# DS3231.net
KiCad netlist of a schematic drawn in Altium Designer
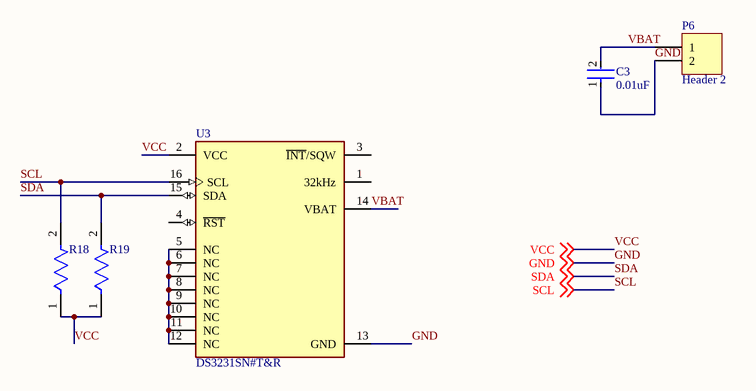
[diagram p0: DS3231.SchDoc]

(export (version "E")
  (design (tool "Eeschema 10.0.6"))
  (components
    (comp (ref "C3")
      (value "0.01uF")
      (footprint "FP-C1206C-EB-MFG")
      (description "1206 C 330nF Ceramic Multilayer Capacitor; 25 VDC; +125degC; X7R Dielec; +/-10%")
      (fields
        (field (name "MANUFACTURER") "KEMET")
        (field (name "MANUFACTURER PART NUMBER") "C1206C334K3RACTU")
      )
      (libsource (lib "Altium Content Vault") (part "b4654b650e69147ec39a6b967a45e02"))
    )
    (comp (ref "P6")
      (value "Header 2")
      (footprint "HDR1X2")
      (description "Header, 2-Pin")
      (fields (field (name "PUBLISHER") "Altium Limited"))
      (libsource (lib "Miscellaneous Connectors") (part "Header 2"))
    )
    (comp (ref "R18")
      (value "~")
      (footprint "FP-CR1206-IPC_B")
      (description "Thick Film Chip Resistors 1206 10kΩ 0.25W 5% 200ppm/°C")
      (fields (field (name "TOLERANCE") "5%"))
      (libsource (lib "Altium Content Vault") (part "1029c3af85768c4190bb7ad29bc67b5"))
    )
    (comp (ref "R19")
      (value "~")
      (footprint "FP-CR1206-IPC_B")
      (description "Thick Film Chip Resistors 1206 10kΩ 0.25W 5% 200ppm/°C")
      (fields (field (name "TOLERANCE") "5%"))
      (libsource (lib "Altium Content Vault") (part "1029c3af85768c4190bb7ad29bc67b5"))
    )
    (comp (ref "U3")
      (value "DS3231SN#T&R")
      (footprint "FP-W16-H2-MFG")
      (description "IC RTC CLK/CALENDAR I2C 16-SOIC")
      (libsource (lib "Altium Content Vault") (part "49e129a02c1e013a88f81c98964c20e"))
    )
  )
  (nets
    (net (code "1") (name "/VBAT") (class "Default")
      (node (ref "C3") (pin "2") (pinfunction "2_2") (pintype "passive"))
      (node (ref "P6") (pin "1") (pinfunction "1_1") (pintype "passive"))
      (node (ref "U3") (pin "14") (pinfunction "VBAT_14") (pintype "power_in"))
    )
    (net (code "2") (name "GND") (class "Default")
      (node (ref "C3") (pin "1") (pinfunction "1_1") (pintype "passive"))
      (node (ref "P6") (pin "2") (pinfunction "2_2") (pintype "passive"))
      (node (ref "U3") (pin "13") (pinfunction "GND_13") (pintype "power_in"))
    )
    (net (code "3") (name "Net-(U3-NC-Pad10)") (class "Default")
      (node (ref "U3") (pin "10") (pinfunction "NC_10") (pintype "passive"))
      (node (ref "U3") (pin "11") (pinfunction "NC_11") (pintype "passive"))
      (node (ref "U3") (pin "12") (pinfunction "NC_12") (pintype "passive"))
      (node (ref "U3") (pin "5") (pinfunction "NC_5") (pintype "passive"))
      (node (ref "U3") (pin "6") (pinfunction "NC_6") (pintype "passive"))
      (node (ref "U3") (pin "7") (pinfunction "NC_7") (pintype "passive"))
      (node (ref "U3") (pin "8") (pinfunction "NC_8") (pintype "passive"))
      (node (ref "U3") (pin "9") (pinfunction "NC_9") (pintype "passive"))
    )
    (net (code "4") (name "SCL") (class "Default")
      (node (ref "R18") (pin "2") (pinfunction "2_2") (pintype "passive"))
      (node (ref "U3") (pin "16") (pinfunction "SCL_16") (pintype "input"))
    )
    (net (code "5") (name "SDA") (class "Default")
      (node (ref "R19") (pin "2") (pinfunction "2_2") (pintype "passive"))
      (node (ref "U3") (pin "15") (pinfunction "SDA_15") (pintype "bidirectional"))
    )
    (net (code "6") (name "VCC") (class "Default")
      (node (ref "R18") (pin "1") (pinfunction "1_1") (pintype "passive"))
      (node (ref "R19") (pin "1") (pinfunction "1_1") (pintype "passive"))
      (node (ref "U3") (pin "2") (pinfunction "VCC_2") (pintype "power_in"))
    )
    (net (code "7") (name "unconnected-(U3-32kHz-Pad1)") (class "Default")
      (node (ref "U3") (pin "1") (pinfunction "32kHz_1") (pintype "open_collector"))
    )
    (net (code "8") (name "unconnected-(U3-~{INT}{slash}SQW-Pad3)") (class "Default")
      (node (ref "U3") (pin "3") (pinfunction "~{INT}/SQW_3") (pintype "open_collector"))
    )
    (net (code "9") (name "unconnected-(U3-~{RST}-Pad4)") (class "Default")
      (node (ref "U3") (pin "4") (pinfunction "~{RST}_4") (pintype "bidirectional"))
    )
  )
)
